# POWR0001_BCR_LT1513.net
KiCad netlist of a schematic drawn in Altium Designer
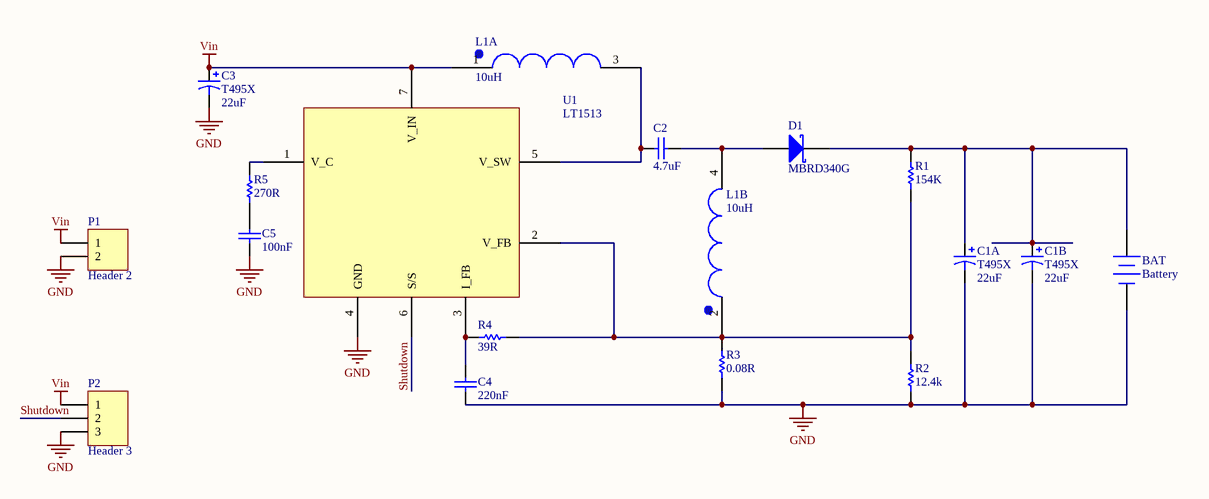
[diagram p0: POWR0001_BCR_LT1513.SchDoc]

(export (version "E")
  (design (tool "Eeschema 10.0.6"))
  (components
    (comp (ref "BAT")
      (value "Battery")
      (footprint "Screw Header 2")
      (description "Multicell Battery")
      (fields (field (name "PUBLISHER") "Altium Limited"))
      (libsource (lib "Miscellaneous Devices") (part "Battery"))
    )
    (comp (ref "C1A")
      (value "T495X")
      (footprint "X")
      (description "Solid Tantalum Chip Capacitor, Standard T495 Series - Low ESR, Surge Robust")
      (fields (field (name "ALTIUM_VALUE") "22uF") (field (name "PUBLISHER") "Altium Limited"))
      (libsource (lib "KEMET Chip Capacitor") (part "T495X"))
    )
    (comp (ref "C1B")
      (value "T495X")
      (footprint "X")
      (description "Solid Tantalum Chip Capacitor, Standard T495 Series - Low ESR, Surge Robust")
      (fields (field (name "ALTIUM_VALUE") "22uF") (field (name "PUBLISHER") "Altium Limited"))
      (libsource (lib "KEMET Chip Capacitor") (part "T495X"))
    )
    (comp (ref "C2")
      (value "4.7uF")
      (footprint "CAPC3225M")
      (description "Capacitor")
      (fields (field (name "Comment") "Cap") (field (name "PUBLISHER") "Altium Limited"))
      (libsource (lib "Miscellaneous Devices") (part "Cap"))
    )
    (comp (ref "C3")
      (value "T495X")
      (footprint "X")
      (description "Solid Tantalum Chip Capacitor, Standard T495 Series - Low ESR, Surge Robust")
      (fields (field (name "ALTIUM_VALUE") "22uF") (field (name "PUBLISHER") "Altium Limited"))
      (libsource (lib "KEMET Chip Capacitor") (part "T495X"))
    )
    (comp (ref "C4")
      (value "220nF")
      (footprint "CAPC3216M")
      (description "Capacitor")
      (fields (field (name "Comment") "Cap") (field (name "PUBLISHER") "Altium Limited"))
      (libsource (lib "Miscellaneous Devices") (part "Cap"))
    )
    (comp (ref "C5")
      (value "100nF")
      (footprint "CAPC3216M")
      (description "Capacitor")
      (fields (field (name "Comment") "Cap") (field (name "PUBLISHER") "Altium Limited"))
      (libsource (lib "Miscellaneous Devices") (part "Cap"))
    )
    (comp (ref "D1")
      (value "MBRD340G")
      (footprint "TO229P990X238-3N")
      (description "Schottky Rectifier")
      (fields (field (name "PUBLISHER") "Altium Limited"))
      (libsource (lib "Miscellaneous Devices") (part "Diode 11DQ03"))
    )
    (comp (ref "L1")
      (value "10uH")
      (footprint "DRQ125")
      (fields (field (name "Comment") "DRQ125 Dual Inductor"))
      (libsource (lib "LT1513") (part "DRQ125 Dual Inductor"))
    )
    (comp (ref "P1")
      (value "Header 2")
      (footprint "Screw Header 2")
      (description "Header, 2-Pin")
      (fields (field (name "PUBLISHER") "Altium Limited"))
      (libsource (lib "Miscellaneous Connectors") (part "Header 2"))
    )
    (comp (ref "P2")
      (value "Header 3")
      (footprint "HDR1X3")
      (description "Header, 3-Pin")
      (fields (field (name "PUBLISHER") "Altium Limited"))
      (libsource (lib "Miscellaneous Connectors") (part "Header 3"))
    )
    (comp (ref "R1")
      (value "154K")
      (footprint "RESC3216M")
      (description "Resistor")
      (fields (field (name "Comment") "Res1") (field (name "PUBLISHER") "Altium Limited"))
      (libsource (lib "Miscellaneous Devices") (part "Res1"))
    )
    (comp (ref "R2")
      (value "12.4k")
      (footprint "RESC3216M")
      (description "Resistor")
      (fields (field (name "Comment") "Res1") (field (name "PUBLISHER") "Altium Limited"))
      (libsource (lib "Miscellaneous Devices") (part "Res1"))
    )
    (comp (ref "R3")
      (value "0.08R")
      (footprint "RESC3216M")
      (description "Resistor")
      (fields (field (name "Comment") "Res1") (field (name "PUBLISHER") "Altium Limited"))
      (libsource (lib "Miscellaneous Devices") (part "Res1"))
    )
    (comp (ref "R4")
      (value "39R")
      (footprint "RESC3216M")
      (description "Resistor")
      (fields (field (name "Comment") "Res1") (field (name "PUBLISHER") "Altium Limited"))
      (libsource (lib "Miscellaneous Devices") (part "Res1"))
    )
    (comp (ref "R5")
      (value "270R")
      (footprint "RESC3216M")
      (description "Resistor")
      (fields (field (name "Comment") "Res1") (field (name "PUBLISHER") "Altium Limited"))
      (libsource (lib "Miscellaneous Devices") (part "Res1"))
    )
    (comp (ref "U1")
      (value "LT1513")
      (footprint "TO152P1396X238-8N")
      (libsource (lib "LT1513") (part "LT1513"))
    )
  )
  (nets
    (net (code "1") (name "/Shutdown") (class "Default")
      (node (ref "P2") (pin "2") (pinfunction "2_2") (pintype "passive"))
      (node (ref "U1") (pin "6") (pinfunction "S/S_6") (pintype "passive"))
    )
    (net (code "2") (name "GND") (class "Default")
      (node (ref "BAT") (pin "2") (pinfunction "-_2") (pintype "passive"))
      (node (ref "C1A") (pin "2") (pinfunction "2_2") (pintype "passive"))
      (node (ref "C1B") (pin "2") (pinfunction "2_2") (pintype "passive"))
      (node (ref "C3") (pin "2") (pinfunction "2_2") (pintype "passive"))
      (node (ref "C4") (pin "2") (pinfunction "2_2") (pintype "passive"))
      (node (ref "C5") (pin "2") (pinfunction "2_2") (pintype "passive"))
      (node (ref "P1") (pin "2") (pinfunction "2_2") (pintype "passive"))
      (node (ref "P2") (pin "3") (pinfunction "3_3") (pintype "passive"))
      (node (ref "R2") (pin "1") (pinfunction "1_1") (pintype "passive"))
      (node (ref "R3") (pin "1") (pinfunction "1_1") (pintype "passive"))
      (node (ref "U1") (pin "4") (pinfunction "GND_4") (pintype "passive"))
    )
    (net (code "3") (name "Net-(BAT-+)") (class "Default")
      (node (ref "BAT") (pin "1") (pinfunction "+_1") (pintype "passive"))
      (node (ref "C1A") (pin "1") (pinfunction "1_1") (pintype "passive"))
      (node (ref "C1B") (pin "1") (pinfunction "1_1") (pintype "passive"))
      (node (ref "D1") (pin "2") (pinfunction "K_2") (pintype "passive"))
      (node (ref "R1") (pin "2") (pinfunction "2_2") (pintype "passive"))
    )
    (net (code "4") (name "Net-(C5-Pad1)") (class "Default")
      (node (ref "C5") (pin "1") (pinfunction "1_1") (pintype "passive"))
      (node (ref "R5") (pin "2") (pinfunction "2_2") (pintype "passive"))
    )
    (net (code "5") (name "Net-(D1-A)") (class "Default")
      (node (ref "C2") (pin "1") (pinfunction "1_1") (pintype "passive"))
      (node (ref "D1") (pin "1") (pinfunction "A_1") (pintype "passive"))
      (node (ref "L1") (pin "4") (pinfunction "18_4") (pintype "passive"))
    )
    (net (code "6") (name "Net-(L1A-18)") (class "Default")
      (node (ref "C2") (pin "2") (pinfunction "2_2") (pintype "passive"))
      (node (ref "L1") (pin "3") (pinfunction "18_3") (pintype "passive"))
      (node (ref "U1") (pin "5") (pinfunction "V_SW_5") (pintype "passive"))
    )
    (net (code "7") (name "Net-(L1B-17)") (class "Default")
      (node (ref "L1") (pin "2") (pinfunction "17_2") (pintype "passive"))
      (node (ref "R1") (pin "1") (pinfunction "1_1") (pintype "passive"))
      (node (ref "R2") (pin "2") (pinfunction "2_2") (pintype "passive"))
      (node (ref "R3") (pin "2") (pinfunction "2_2") (pintype "passive"))
      (node (ref "R4") (pin "1") (pinfunction "1_1") (pintype "passive"))
      (node (ref "U1") (pin "2") (pinfunction "V_FB_2") (pintype "passive"))
    )
    (net (code "8") (name "Net-(U1-I_FB)") (class "Default")
      (node (ref "C4") (pin "1") (pinfunction "1_1") (pintype "passive"))
      (node (ref "R4") (pin "2") (pinfunction "2_2") (pintype "passive"))
      (node (ref "U1") (pin "3") (pinfunction "I_FB_3") (pintype "passive"))
    )
    (net (code "9") (name "Net-(U1-V_C)") (class "Default")
      (node (ref "R5") (pin "1") (pinfunction "1_1") (pintype "passive"))
      (node (ref "U1") (pin "1") (pinfunction "V_C_1") (pintype "passive"))
    )
    (net (code "10") (name "Vin") (class "Default")
      (node (ref "C3") (pin "1") (pinfunction "1_1") (pintype "passive"))
      (node (ref "L1") (pin "1") (pinfunction "17_1") (pintype "passive"))
      (node (ref "P1") (pin "1") (pinfunction "1_1") (pintype "passive"))
      (node (ref "P2") (pin "1") (pinfunction "1_1") (pintype "passive"))
      (node (ref "U1") (pin "7") (pinfunction "V_IN_7") (pintype "passive"))
    )
  )
)
